# Schematic.net
KiCad netlist of a schematic drawn in Altium Designer
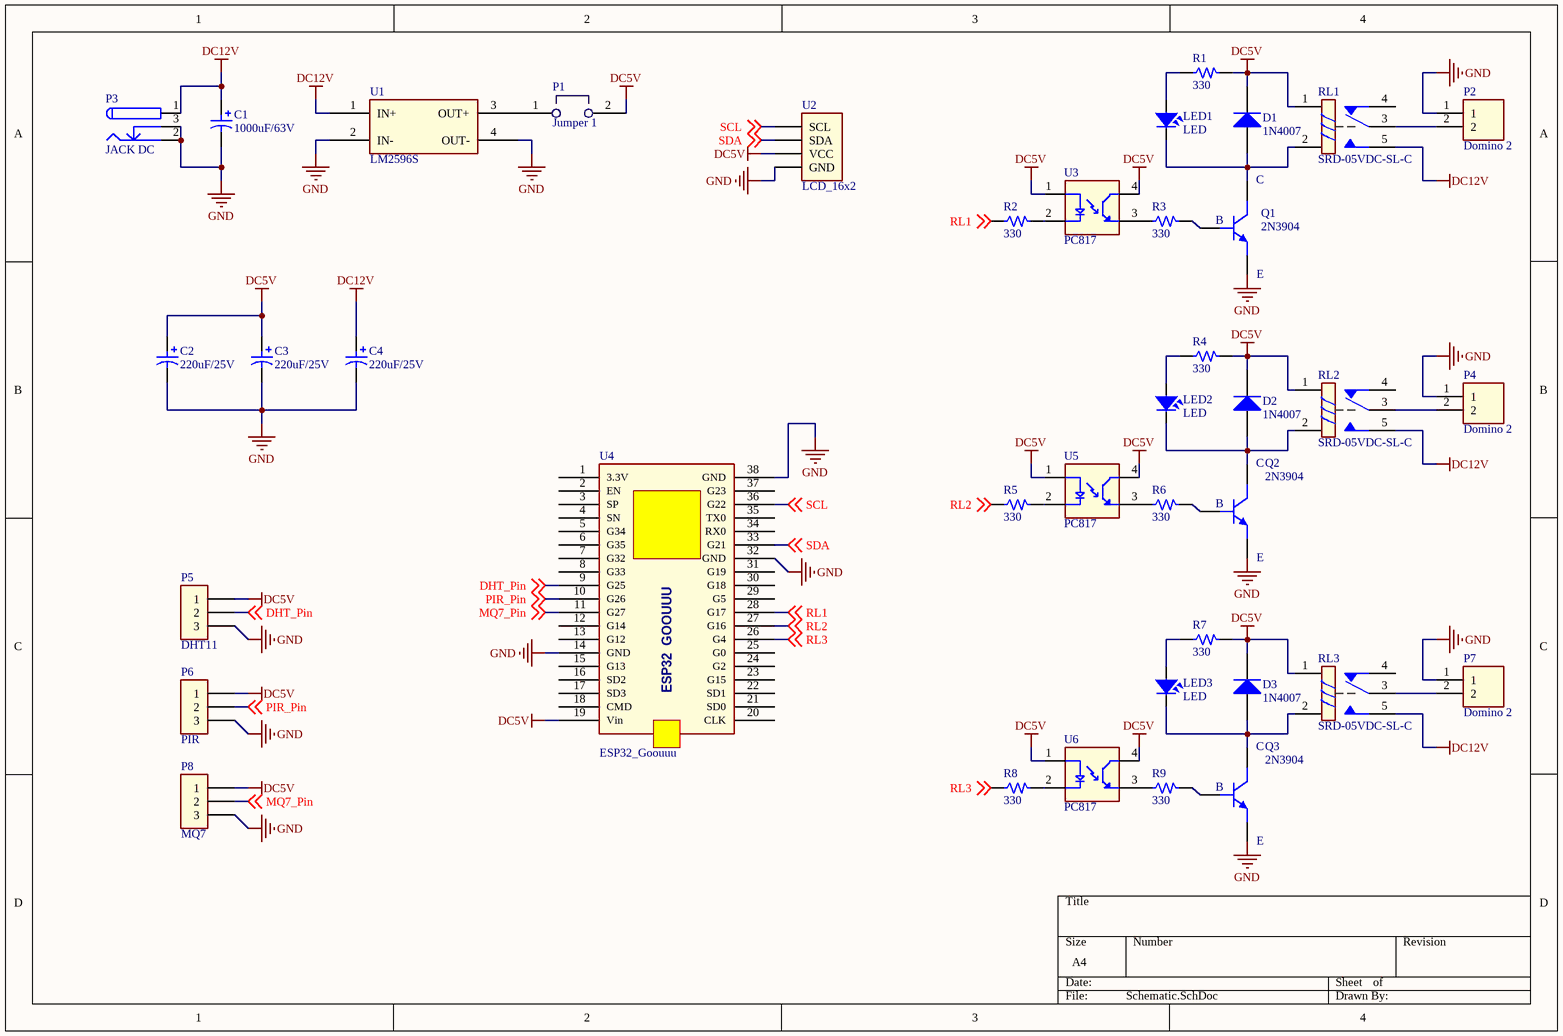
[diagram p0: Schematic.SchDoc]

(export (version "E")
  (design (tool "Eeschema 10.0.6"))
  (components
    (comp (ref "C1")
      (value "1000uF/63V")
      (footprint "CAP-ALUM-12.5x25")
      (description "Capacitor Aluminum 1000uF 20% 50V Radial")
      (libsource (lib "SachTran_Lib") (part "EEUHD1H102B"))
    )
    (comp (ref "C2")
      (value "220uF/25V")
      (footprint "CAP-ALUM-10x12.5")
      (description "Capacitor Aluminum 220uF 20% 25V Radial")
      (libsource (lib "SachTran_Lib") (part "EEUTA1E221"))
    )
    (comp (ref "C3")
      (value "220uF/25V")
      (footprint "CAP-ALUM-10x12.5")
      (description "Capacitor Aluminum 220uF 20% 25V Radial")
      (libsource (lib "SachTran_Lib") (part "EEUTA1E221"))
    )
    (comp (ref "C4")
      (value "220uF/25V")
      (footprint "CAP-ALUM-10x12.5")
      (description "Capacitor Aluminum 220uF 20% 25V Radial")
      (libsource (lib "SachTran_Lib") (part "EEUTA1E221"))
    )
    (comp (ref "D1")
      (value "1N4007")
      (footprint "DO-41")
      (description "Diode 1N4007")
      (libsource (lib "SachTran_Lib") (part "1N4007"))
    )
    (comp (ref "D2")
      (value "1N4007")
      (footprint "DO-41")
      (description "Diode 1N4007")
      (libsource (lib "SachTran_Lib") (part "1N4007"))
    )
    (comp (ref "D3")
      (value "1N4007")
      (footprint "DO-41")
      (description "Diode 1N4007")
      (libsource (lib "SachTran_Lib") (part "1N4007"))
    )
    (comp (ref "LED1")
      (value "LED")
      (footprint "LED-5mm-Red")
      (description "LED Single colour")
      (libsource (lib "SachTran_Lib") (part "LED-5MM"))
    )
    (comp (ref "LED2")
      (value "LED")
      (footprint "LED-5mm-Red")
      (description "LED Single colour")
      (libsource (lib "SachTran_Lib") (part "LED-5MM"))
    )
    (comp (ref "LED3")
      (value "LED")
      (footprint "LED-5mm-Red")
      (description "LED Single colour")
      (libsource (lib "SachTran_Lib") (part "LED-5MM"))
    )
    (comp (ref "P1")
      (value "Jumper 1")
      (footprint "Jumper-1")
      (libsource (lib "SachTran_Lib") (part "Jumper-1"))
    )
    (comp (ref "P2")
      (value "Domino 2")
      (footprint "Domino-2")
      (libsource (lib "SachTran_Lib") (part "Domino-2"))
    )
    (comp (ref "P3")
      (value "JACK DC")
      (footprint "DC5.5/2.1")
      (description "Low Voltage Power Supply Connector")
      (libsource (lib "SachTran_Lib") (part "DC-5.5/2.1"))
    )
    (comp (ref "P4")
      (value "Domino 2")
      (footprint "Domino-2")
      (libsource (lib "SachTran_Lib") (part "Domino-2"))
    )
    (comp (ref "P5")
      (value "DHT11")
      (footprint "B3B-XH-A")
      (description "Connector Header Through Hole 3 position 0.098\" (2.50mm)")
      (libsource (lib "SachTran_Lib") (part "B3B-XH-A"))
    )
    (comp (ref "P6")
      (value "PIR")
      (footprint "B3B-XH-A")
      (description "Connector Header Through Hole 3 position 0.098\" (2.50mm)")
      (libsource (lib "SachTran_Lib") (part "B3B-XH-A"))
    )
    (comp (ref "P7")
      (value "Domino 2")
      (footprint "Domino-2")
      (libsource (lib "SachTran_Lib") (part "Domino-2"))
    )
    (comp (ref "P8")
      (value "MQ7")
      (footprint "B3B-XH-A")
      (description "Connector Header Through Hole 3 position 0.098\" (2.50mm)")
      (libsource (lib "SachTran_Lib") (part "B3B-XH-A"))
    )
    (comp (ref "Q1")
      (value "2N3904")
      (footprint "TO92-3")
      (description "Bipolar (BJT) Transistor NPN 40V 200 mA 300MHz 625 mW Through Hole TO-92")
      (libsource (lib "SachTran_Lib") (part "2N3904"))
    )
    (comp (ref "Q2")
      (value "2N3904")
      (footprint "TO92-3")
      (description "Bipolar (BJT) Transistor NPN 40V 200 mA 300MHz 625 mW Through Hole TO-92")
      (libsource (lib "SachTran_Lib") (part "2N3904"))
    )
    (comp (ref "Q3")
      (value "2N3904")
      (footprint "TO92-3")
      (description "Bipolar (BJT) Transistor NPN 40V 200 mA 300MHz 625 mW Through Hole TO-92")
      (libsource (lib "SachTran_Lib") (part "2N3904"))
    )
    (comp (ref "R1")
      (value "330")
      (footprint "R1/4W-H2")
      (description "Resistor 1/4W Through Hole")
      (libsource (lib "SachTran_Lib") (part "RES-1/4W"))
    )
    (comp (ref "R2")
      (value "330")
      (footprint "R1/4W-H2")
      (description "Resistor 1/4W Through Hole")
      (libsource (lib "SachTran_Lib") (part "RES-1/4W"))
    )
    (comp (ref "R3")
      (value "330")
      (footprint "R1/4W-H2")
      (description "Resistor 1/4W Through Hole")
      (libsource (lib "SachTran_Lib") (part "RES-1/4W"))
    )
    (comp (ref "R4")
      (value "330")
      (footprint "R1/4W-H2")
      (description "Resistor 1/4W Through Hole")
      (libsource (lib "SachTran_Lib") (part "RES-1/4W"))
    )
    (comp (ref "R5")
      (value "330")
      (footprint "R1/4W-H2")
      (description "Resistor 1/4W Through Hole")
      (libsource (lib "SachTran_Lib") (part "RES-1/4W"))
    )
    (comp (ref "R6")
      (value "330")
      (footprint "R1/4W-H2")
      (description "Resistor 1/4W Through Hole")
      (libsource (lib "SachTran_Lib") (part "RES-1/4W"))
    )
    (comp (ref "R7")
      (value "330")
      (footprint "R1/4W-H2")
      (description "Resistor 1/4W Through Hole")
      (libsource (lib "SachTran_Lib") (part "RES-1/4W"))
    )
    (comp (ref "R8")
      (value "330")
      (footprint "R1/4W-H2")
      (description "Resistor 1/4W Through Hole")
      (libsource (lib "SachTran_Lib") (part "RES-1/4W"))
    )
    (comp (ref "R9")
      (value "330")
      (footprint "R1/4W-H2")
      (description "Resistor 1/4W Through Hole")
      (libsource (lib "SachTran_Lib") (part "RES-1/4W"))
    )
    (comp (ref "RL1")
      (value "SRD-05VDC-SL-C")
      (footprint "SRD-05VDC-SL-C")
      (description "Relay 5V")
      (libsource (lib "SachTran_Lib") (part "SRD-05VDC-SL-C"))
    )
    (comp (ref "RL2")
      (value "SRD-05VDC-SL-C")
      (footprint "SRD-05VDC-SL-C")
      (description "Relay 5V")
      (libsource (lib "SachTran_Lib") (part "SRD-05VDC-SL-C"))
    )
    (comp (ref "RL3")
      (value "SRD-05VDC-SL-C")
      (footprint "SRD-05VDC-SL-C")
      (description "Relay 5V")
      (libsource (lib "SachTran_Lib") (part "SRD-05VDC-SL-C"))
    )
    (comp (ref "U1")
      (value "LM2596S")
      (footprint "Module-LM2596S")
      (description "Module LM2596S")
      (libsource (lib "SachTran_Lib") (part "Module-LM2596S"))
    )
    (comp (ref "U2")
      (value "LCD_16x2")
      (footprint "LCD-I2C-16X2 (1)")
      (description "LCD-I2C-16X2")
      (libsource (lib "SachTran_Lib") (part "LCD-I2C-16X2"))
    )
    (comp (ref "U3")
      (value "PC817")
      (footprint "DIP-4")
      (description "Optoisolator Transistor Output 1 Channel 4")
      (libsource (lib "SachTran_Lib") (part "PC817"))
    )
    (comp (ref "U4")
      (value "ESP32_Goouuu")
      (footprint "Kit-ESP32-GOOUUU")
      (description "Kit ESP32 Goouuu")
      (libsource (lib "SachTran_Lib") (part "Kit-ESP32-Goouuu"))
    )
    (comp (ref "U5")
      (value "PC817")
      (footprint "DIP-4")
      (description "Optoisolator Transistor Output 1 Channel 4")
      (libsource (lib "SachTran_Lib") (part "PC817"))
    )
    (comp (ref "U6")
      (value "PC817")
      (footprint "DIP-4")
      (description "Optoisolator Transistor Output 1 Channel 4")
      (libsource (lib "SachTran_Lib") (part "PC817"))
    )
  )
  (nets
    (net (code "1") (name "DC5V") (class "Default")
      (node (ref "C2") (pin "1") (pinfunction "1_1") (pintype "passive"))
      (node (ref "C3") (pin "1") (pinfunction "1_1") (pintype "passive"))
      (node (ref "D1") (pin "2") (pinfunction "K_2") (pintype "passive"))
      (node (ref "D2") (pin "2") (pinfunction "K_2") (pintype "passive"))
      (node (ref "D3") (pin "2") (pinfunction "K_2") (pintype "passive"))
      (node (ref "P1") (pin "2") (pinfunction "2_2") (pintype "passive"))
      (node (ref "P5") (pin "1") (pinfunction "1_1") (pintype "passive"))
      (node (ref "P6") (pin "1") (pinfunction "1_1") (pintype "passive"))
      (node (ref "P8") (pin "1") (pinfunction "1_1") (pintype "passive"))
      (node (ref "R1") (pin "2") (pinfunction "2_2") (pintype "passive"))
      (node (ref "R4") (pin "2") (pinfunction "2_2") (pintype "passive"))
      (node (ref "R7") (pin "2") (pinfunction "2_2") (pintype "passive"))
      (node (ref "RL1") (pin "1") (pinfunction "1_1") (pintype "passive"))
      (node (ref "RL2") (pin "1") (pinfunction "1_1") (pintype "passive"))
      (node (ref "RL3") (pin "1") (pinfunction "1_1") (pintype "passive"))
      (node (ref "U2") (pin "3") (pinfunction "VCC_3") (pintype "passive"))
      (node (ref "U3") (pin "1") (pinfunction "A_1") (pintype "passive"))
      (node (ref "U3") (pin "4") (pinfunction "CT_4") (pintype "passive"))
      (node (ref "U4") (pin "19") (pinfunction "Vin_19") (pintype "passive"))
      (node (ref "U5") (pin "1") (pinfunction "A_1") (pintype "passive"))
      (node (ref "U5") (pin "4") (pinfunction "CT_4") (pintype "passive"))
      (node (ref "U6") (pin "1") (pinfunction "A_1") (pintype "passive"))
      (node (ref "U6") (pin "4") (pinfunction "CT_4") (pintype "passive"))
    )
    (net (code "2") (name "DC12V") (class "Default")
      (node (ref "C1") (pin "1") (pinfunction "1_1") (pintype "passive"))
      (node (ref "C4") (pin "1") (pinfunction "1_1") (pintype "passive"))
      (node (ref "P3") (pin "1") (pinfunction "1_1") (pintype "power_in"))
      (node (ref "RL1") (pin "5") (pinfunction "5_5") (pintype "passive"))
      (node (ref "RL2") (pin "5") (pinfunction "5_5") (pintype "passive"))
      (node (ref "RL3") (pin "5") (pinfunction "5_5") (pintype "passive"))
      (node (ref "U1") (pin "1") (pinfunction "IN+_1") (pintype "passive"))
    )
    (net (code "3") (name "DHT_Pin") (class "Default")
      (node (ref "P5") (pin "2") (pinfunction "2_2") (pintype "passive"))
      (node (ref "U4") (pin "9") (pinfunction "G25_9") (pintype "passive"))
    )
    (net (code "4") (name "GND") (class "Default")
      (node (ref "C1") (pin "2") (pinfunction "2_2") (pintype "passive"))
      (node (ref "C2") (pin "2") (pinfunction "2_2") (pintype "passive"))
      (node (ref "C3") (pin "2") (pinfunction "2_2") (pintype "passive"))
      (node (ref "C4") (pin "2") (pinfunction "2_2") (pintype "passive"))
      (node (ref "P2") (pin "1") (pinfunction "1_1") (pintype "passive"))
      (node (ref "P3") (pin "2") (pinfunction "2_2") (pintype "power_in"))
      (node (ref "P3") (pin "3") (pinfunction "3_3") (pintype "power_in"))
      (node (ref "P4") (pin "1") (pinfunction "1_1") (pintype "passive"))
      (node (ref "P5") (pin "3") (pinfunction "3_3") (pintype "passive"))
      (node (ref "P6") (pin "3") (pinfunction "3_3") (pintype "passive"))
      (node (ref "P7") (pin "1") (pinfunction "1_1") (pintype "passive"))
      (node (ref "P8") (pin "3") (pinfunction "3_3") (pintype "passive"))
      (node (ref "Q1") (pin "1") (pinfunction "E_1") (pintype "passive"))
      (node (ref "Q2") (pin "1") (pinfunction "E_1") (pintype "passive"))
      (node (ref "Q3") (pin "1") (pinfunction "E_1") (pintype "passive"))
      (node (ref "U1") (pin "2") (pinfunction "IN-_2") (pintype "passive"))
      (node (ref "U1") (pin "4") (pinfunction "OUT-_4") (pintype "passive"))
      (node (ref "U2") (pin "4") (pinfunction "GND_4") (pintype "passive"))
      (node (ref "U4") (pin "14") (pinfunction "GND_14") (pintype "passive"))
      (node (ref "U4") (pin "32") (pinfunction "GND_32") (pintype "passive"))
      (node (ref "U4") (pin "38") (pinfunction "GND_38") (pintype "passive"))
    )
    (net (code "5") (name "MQ7_Pin") (class "Default")
      (node (ref "P8") (pin "2") (pinfunction "2_2") (pintype "passive"))
      (node (ref "U4") (pin "11") (pinfunction "G27_11") (pintype "passive"))
    )
    (net (code "6") (name "Net-(D1-A)") (class "Default")
      (node (ref "D1") (pin "1") (pinfunction "A_1") (pintype "passive"))
      (node (ref "LED1") (pin "2") (pinfunction "2_2") (pintype "passive"))
      (node (ref "Q1") (pin "3") (pinfunction "C_3") (pintype "passive"))
      (node (ref "RL1") (pin "2") (pinfunction "2_2") (pintype "passive"))
    )
    (net (code "7") (name "Net-(D2-A)") (class "Default")
      (node (ref "D2") (pin "1") (pinfunction "A_1") (pintype "passive"))
      (node (ref "LED2") (pin "2") (pinfunction "2_2") (pintype "passive"))
      (node (ref "Q2") (pin "3") (pinfunction "C_3") (pintype "passive"))
      (node (ref "RL2") (pin "2") (pinfunction "2_2") (pintype "passive"))
    )
    (net (code "8") (name "Net-(D3-A)") (class "Default")
      (node (ref "D3") (pin "1") (pinfunction "A_1") (pintype "passive"))
      (node (ref "LED3") (pin "2") (pinfunction "2_2") (pintype "passive"))
      (node (ref "Q3") (pin "3") (pinfunction "C_3") (pintype "passive"))
      (node (ref "RL3") (pin "2") (pinfunction "2_2") (pintype "passive"))
    )
    (net (code "9") (name "Net-(LED1-Pad1)") (class "Default")
      (node (ref "LED1") (pin "1") (pinfunction "1_1") (pintype "passive"))
      (node (ref "R1") (pin "1") (pinfunction "1_1") (pintype "passive"))
    )
    (net (code "10") (name "Net-(LED2-Pad1)") (class "Default")
      (node (ref "LED2") (pin "1") (pinfunction "1_1") (pintype "passive"))
      (node (ref "R4") (pin "1") (pinfunction "1_1") (pintype "passive"))
    )
    (net (code "11") (name "Net-(LED3-Pad1)") (class "Default")
      (node (ref "LED3") (pin "1") (pinfunction "1_1") (pintype "passive"))
      (node (ref "R7") (pin "1") (pinfunction "1_1") (pintype "passive"))
    )
    (net (code "12") (name "Net-(P2-Pad2)") (class "Default")
      (node (ref "P2") (pin "2") (pinfunction "2_2") (pintype "passive"))
      (node (ref "RL1") (pin "3") (pinfunction "3_3") (pintype "passive"))
    )
    (net (code "13") (name "Net-(P4-Pad2)") (class "Default")
      (node (ref "P4") (pin "2") (pinfunction "2_2") (pintype "passive"))
      (node (ref "RL2") (pin "3") (pinfunction "3_3") (pintype "passive"))
    )
    (net (code "14") (name "Net-(P7-Pad2)") (class "Default")
      (node (ref "P7") (pin "2") (pinfunction "2_2") (pintype "passive"))
      (node (ref "RL3") (pin "3") (pinfunction "3_3") (pintype "passive"))
    )
    (net (code "15") (name "Net-(Q1-B)") (class "Default")
      (node (ref "Q1") (pin "2") (pinfunction "B_2") (pintype "passive"))
      (node (ref "R3") (pin "2") (pinfunction "2_2") (pintype "passive"))
    )
    (net (code "16") (name "Net-(Q2-B)") (class "Default")
      (node (ref "Q2") (pin "2") (pinfunction "B_2") (pintype "passive"))
      (node (ref "R6") (pin "2") (pinfunction "2_2") (pintype "passive"))
    )
    (net (code "17") (name "Net-(Q3-B)") (class "Default")
      (node (ref "Q3") (pin "2") (pinfunction "B_2") (pintype "passive"))
      (node (ref "R9") (pin "2") (pinfunction "2_2") (pintype "passive"))
    )
    (net (code "18") (name "Net-(U1-OUT+)") (class "Default")
      (node (ref "P1") (pin "1") (pinfunction "1_1") (pintype "passive"))
      (node (ref "U1") (pin "3") (pinfunction "OUT+_3") (pintype "passive"))
    )
    (net (code "19") (name "Net-(U3-C)") (class "Default")
      (node (ref "R2") (pin "2") (pinfunction "2_2") (pintype "passive"))
      (node (ref "U3") (pin "2") (pinfunction "C_2") (pintype "passive"))
    )
    (net (code "20") (name "Net-(U3-ET)") (class "Default")
      (node (ref "R3") (pin "1") (pinfunction "1_1") (pintype "passive"))
      (node (ref "U3") (pin "3") (pinfunction "ET_3") (pintype "passive"))
    )
    (net (code "21") (name "Net-(U5-C)") (class "Default")
      (node (ref "R5") (pin "2") (pinfunction "2_2") (pintype "passive"))
      (node (ref "U5") (pin "2") (pinfunction "C_2") (pintype "passive"))
    )
    (net (code "22") (name "Net-(U5-ET)") (class "Default")
      (node (ref "R6") (pin "1") (pinfunction "1_1") (pintype "passive"))
      (node (ref "U5") (pin "3") (pinfunction "ET_3") (pintype "passive"))
    )
    (net (code "23") (name "Net-(U6-C)") (class "Default")
      (node (ref "R8") (pin "2") (pinfunction "2_2") (pintype "passive"))
      (node (ref "U6") (pin "2") (pinfunction "C_2") (pintype "passive"))
    )
    (net (code "24") (name "Net-(U6-ET)") (class "Default")
      (node (ref "R9") (pin "1") (pinfunction "1_1") (pintype "passive"))
      (node (ref "U6") (pin "3") (pinfunction "ET_3") (pintype "passive"))
    )
    (net (code "25") (name "PIR_Pin") (class "Default")
      (node (ref "P6") (pin "2") (pinfunction "2_2") (pintype "passive"))
      (node (ref "U4") (pin "10") (pinfunction "G26_10") (pintype "passive"))
    )
    (net (code "26") (name "RL1") (class "Default")
      (node (ref "R2") (pin "1") (pinfunction "1_1") (pintype "passive"))
      (node (ref "U4") (pin "28") (pinfunction "G17_28") (pintype "passive"))
    )
    (net (code "27") (name "RL2") (class "Default")
      (node (ref "R5") (pin "1") (pinfunction "1_1") (pintype "passive"))
      (node (ref "U4") (pin "27") (pinfunction "G16_27") (pintype "passive"))
    )
    (net (code "28") (name "RL3") (class "Default")
      (node (ref "R8") (pin "1") (pinfunction "1_1") (pintype "passive"))
      (node (ref "U4") (pin "26") (pinfunction "G4_26") (pintype "passive"))
    )
    (net (code "29") (name "SCL") (class "Default")
      (node (ref "U2") (pin "1") (pinfunction "SCL_1") (pintype "passive"))
      (node (ref "U4") (pin "36") (pinfunction "G22_36") (pintype "passive"))
    )
    (net (code "30") (name "SDA") (class "Default")
      (node (ref "U2") (pin "2") (pinfunction "SDA_2") (pintype "passive"))
      (node (ref "U4") (pin "33") (pinfunction "G21_33") (pintype "passive"))
    )
    (net (code "31") (name "unconnected-(RL1-Pad4)") (class "Default")
      (node (ref "RL1") (pin "4") (pinfunction "4_4") (pintype "passive"))
    )
    (net (code "32") (name "unconnected-(RL2-Pad4)") (class "Default")
      (node (ref "RL2") (pin "4") (pinfunction "4_4") (pintype "passive"))
    )
    (net (code "33") (name "unconnected-(RL3-Pad4)") (class "Default")
      (node (ref "RL3") (pin "4") (pinfunction "4_4") (pintype "passive"))
    )
    (net (code "34") (name "unconnected-(U4-3.3V-Pad1)") (class "Default")
      (node (ref "U4") (pin "1") (pinfunction "3.3V_1") (pintype "passive"))
    )
    (net (code "35") (name "unconnected-(U4-CLK-Pad20)") (class "Default")
      (node (ref "U4") (pin "20") (pinfunction "CLK_20") (pintype "passive"))
    )
    (net (code "36") (name "unconnected-(U4-CMD-Pad18)") (class "Default")
      (node (ref "U4") (pin "18") (pinfunction "CMD_18") (pintype "passive"))
    )
    (net (code "37") (name "unconnected-(U4-EN-Pad2)") (class "Default")
      (node (ref "U4") (pin "2") (pinfunction "EN_2") (pintype "passive"))
    )
    (net (code "38") (name "unconnected-(U4-G0-Pad25)") (class "Default")
      (node (ref "U4") (pin "25") (pinfunction "G0_25") (pintype "passive"))
    )
    (net (code "39") (name "unconnected-(U4-G2-Pad24)") (class "Default")
      (node (ref "U4") (pin "24") (pinfunction "G2_24") (pintype "passive"))
    )
    (net (code "40") (name "unconnected-(U4-G5-Pad29)") (class "Default")
      (node (ref "U4") (pin "29") (pinfunction "G5_29") (pintype "passive"))
    )
    (net (code "41") (name "unconnected-(U4-G12-Pad13)") (class "Default")
      (node (ref "U4") (pin "13") (pinfunction "G12_13") (pintype "passive"))
    )
    (net (code "42") (name "unconnected-(U4-G13-Pad15)") (class "Default")
      (node (ref "U4") (pin "15") (pinfunction "G13_15") (pintype "passive"))
    )
    (net (code "43") (name "unconnected-(U4-G14-Pad12)") (class "Default")
      (node (ref "U4") (pin "12") (pinfunction "G14_12") (pintype "passive"))
    )
    (net (code "44") (name "unconnected-(U4-G15-Pad23)") (class "Default")
      (node (ref "U4") (pin "23") (pinfunction "G15_23") (pintype "passive"))
    )
    (net (code "45") (name "unconnected-(U4-G18-Pad30)") (class "Default")
      (node (ref "U4") (pin "30") (pinfunction "G18_30") (pintype "passive"))
    )
    (net (code "46") (name "unconnected-(U4-G19-Pad31)") (class "Default")
      (node (ref "U4") (pin "31") (pinfunction "G19_31") (pintype "passive"))
    )
    (net (code "47") (name "unconnected-(U4-G23-Pad37)") (class "Default")
      (node (ref "U4") (pin "37") (pinfunction "G23_37") (pintype "passive"))
    )
    (net (code "48") (name "unconnected-(U4-G32-Pad7)") (class "Default")
      (node (ref "U4") (pin "7") (pinfunction "G32_7") (pintype "passive"))
    )
    (net (code "49") (name "unconnected-(U4-G33-Pad8)") (class "Default")
      (node (ref "U4") (pin "8") (pinfunction "G33_8") (pintype "passive"))
    )
    (net (code "50") (name "unconnected-(U4-G34-Pad5)") (class "Default")
      (node (ref "U4") (pin "5") (pinfunction "G34_5") (pintype "passive"))
    )
    (net (code "51") (name "unconnected-(U4-G35-Pad6)") (class "Default")
      (node (ref "U4") (pin "6") (pinfunction "G35_6") (pintype "passive"))
    )
    (net (code "52") (name "unconnected-(U4-RX0-Pad34)") (class "Default")
      (node (ref "U4") (pin "34") (pinfunction "RX0_34") (pintype "passive"))
    )
    (net (code "53") (name "unconnected-(U4-SD0-Pad21)") (class "Default")
      (node (ref "U4") (pin "21") (pinfunction "SD0_21") (pintype "passive"))
    )
    (net (code "54") (name "unconnected-(U4-SD1-Pad22)") (class "Default")
      (node (ref "U4") (pin "22") (pinfunction "SD1_22") (pintype "passive"))
    )
    (net (code "55") (name "unconnected-(U4-SD2-Pad16)") (class "Default")
      (node (ref "U4") (pin "16") (pinfunction "SD2_16") (pintype "passive"))
    )
    (net (code "56") (name "unconnected-(U4-SD3-Pad17)") (class "Default")
      (node (ref "U4") (pin "17") (pinfunction "SD3_17") (pintype "passive"))
    )
    (net (code "57") (name "unconnected-(U4-SN-Pad4)") (class "Default")
      (node (ref "U4") (pin "4") (pinfunction "SN_4") (pintype "passive"))
    )
    (net (code "58") (name "unconnected-(U4-SP-Pad3)") (class "Default")
      (node (ref "U4") (pin "3") (pinfunction "SP_3") (pintype "passive"))
    )
    (net (code "59") (name "unconnected-(U4-TX0-Pad35)") (class "Default")
      (node (ref "U4") (pin "35") (pinfunction "TX0_35") (pintype "passive"))
    )
  )
)
